# Arm_controller_Mega.net
KiCad netlist of a schematic drawn in EAGLE
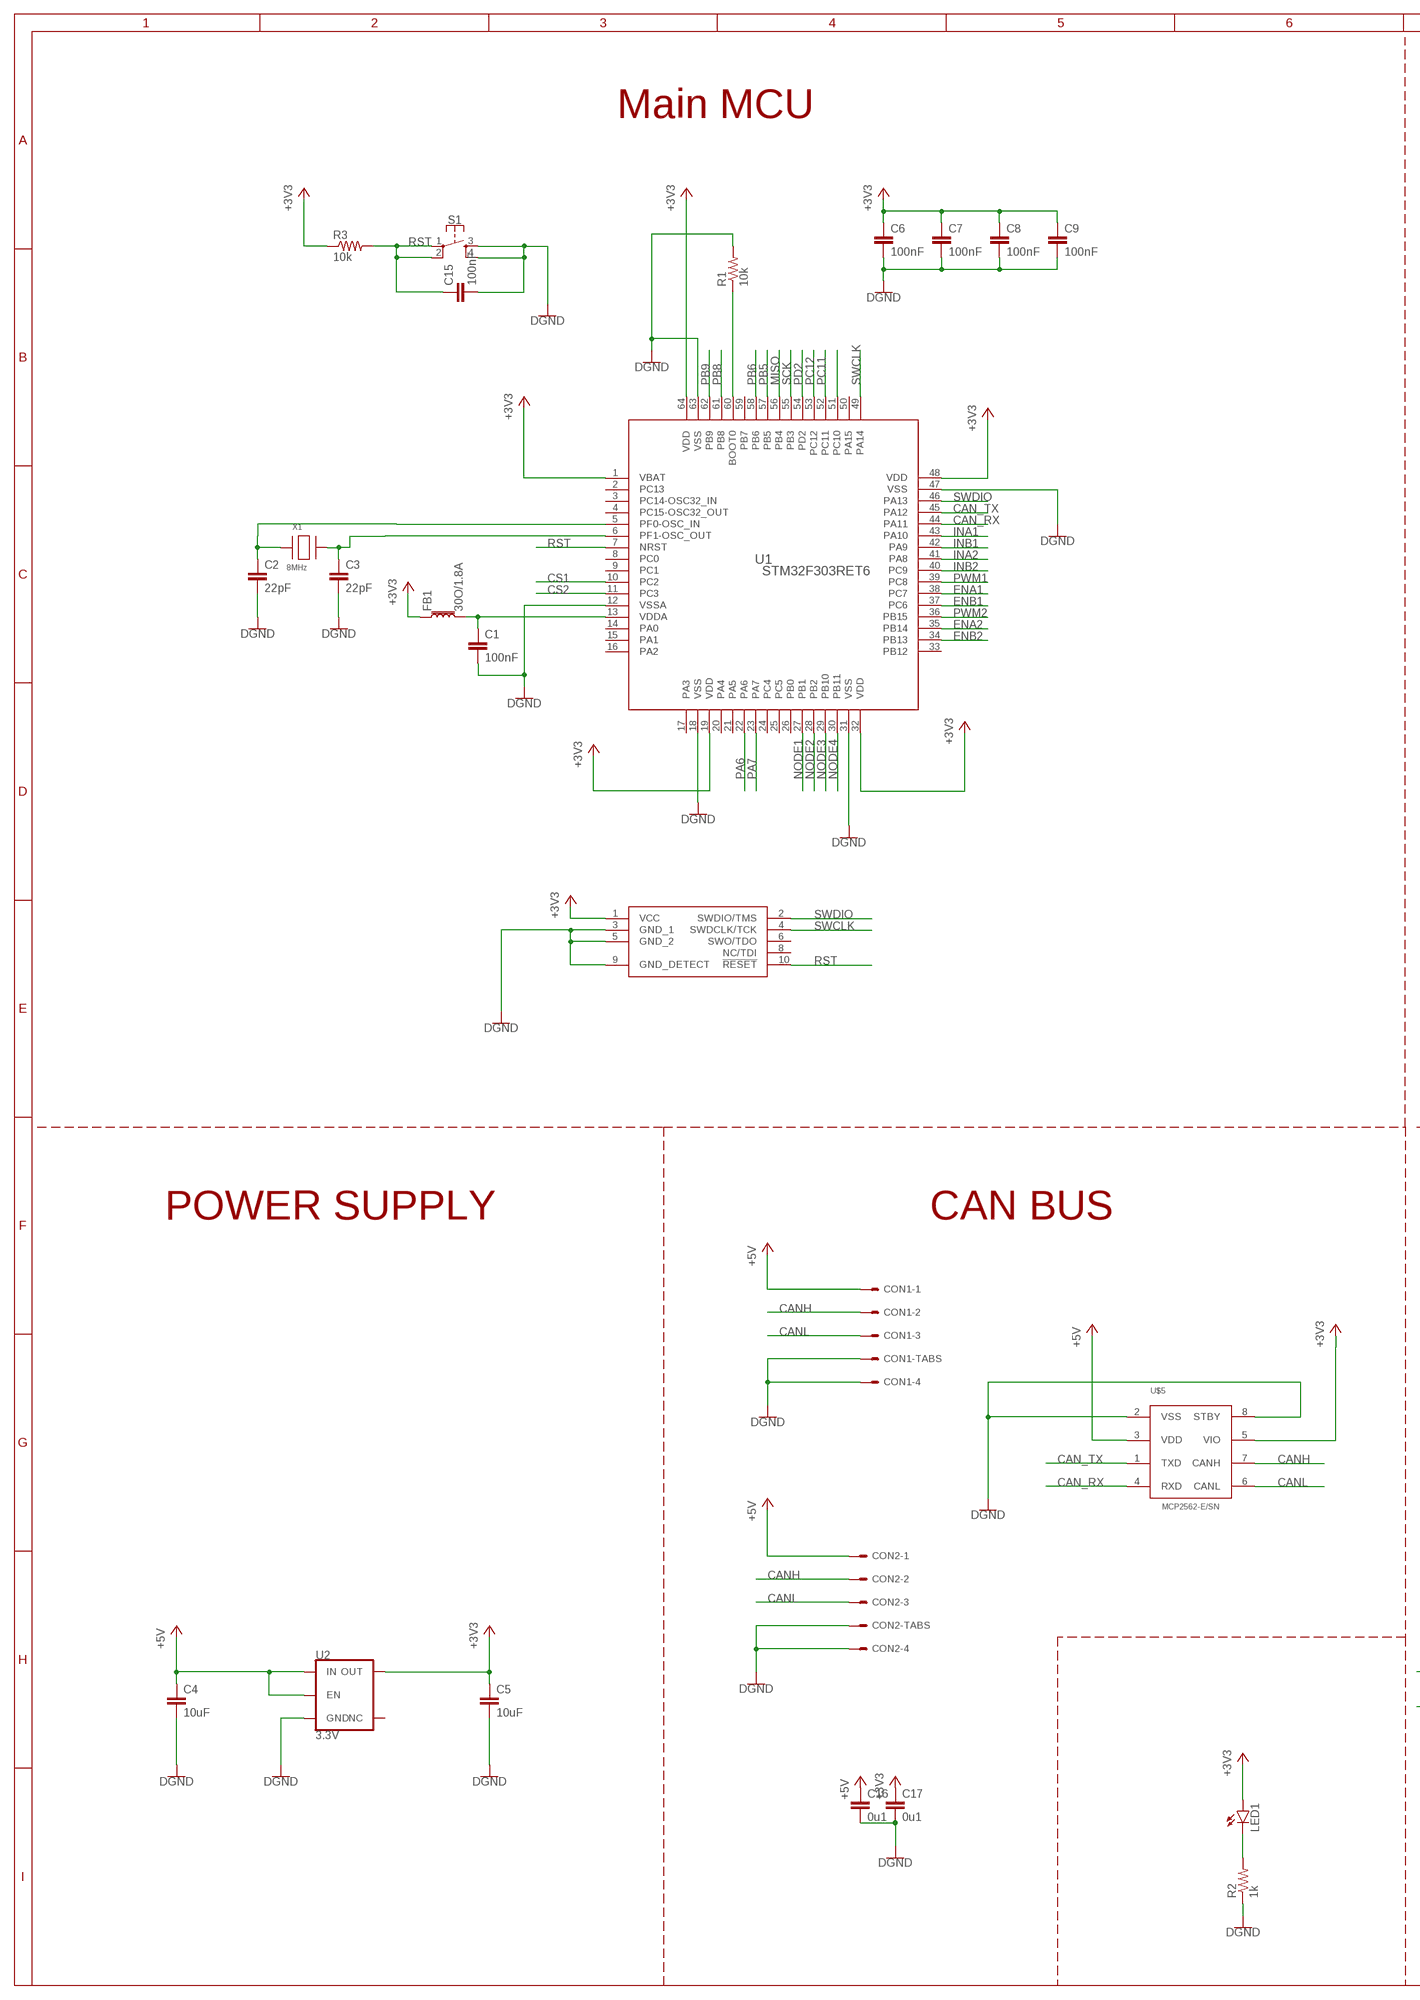
[diagram p0: schematic, sheet 1, part 1 of 2]
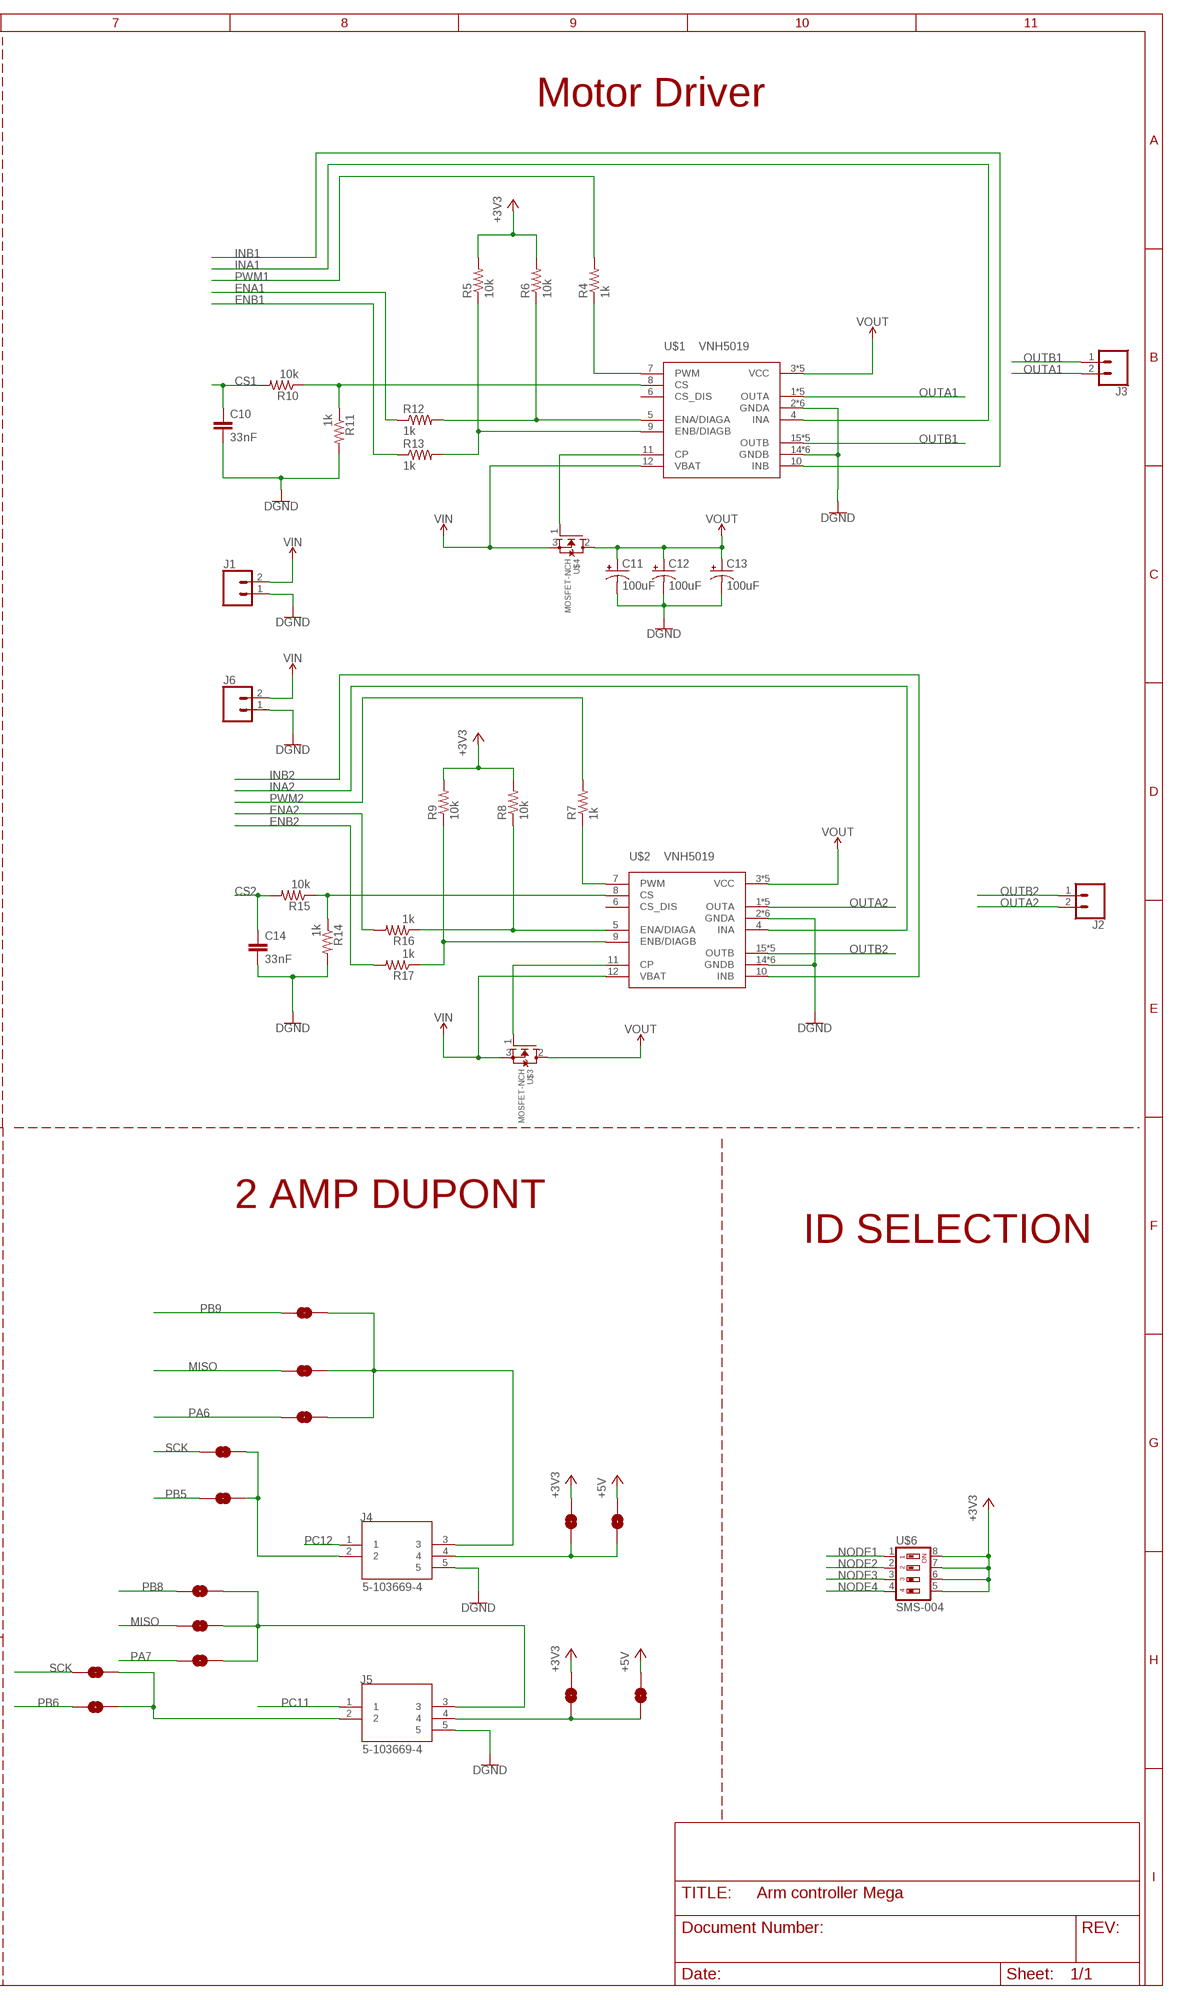
[diagram p1: schematic, sheet 1, part 2 of 2]

(export (version "E")
  (design (tool "Eeschema 10.0.6"))
  (components
    (comp (ref "C1")
      (value "100nF")
      (footprint "eagle-import:C0805")
      (libsource (lib "eagle-import") (part "C-EUC0805"))
    )
    (comp (ref "C2")
      (value "22pF")
      (footprint "eagle-import:C0805")
      (libsource (lib "eagle-import") (part "C-EUC0805"))
    )
    (comp (ref "C3")
      (value "22pF")
      (footprint "eagle-import:C0805")
      (libsource (lib "eagle-import") (part "C-EUC0805"))
    )
    (comp (ref "C4")
      (value "10uF")
      (footprint "eagle-import:C0805")
      (libsource (lib "eagle-import") (part "C-EUC0805"))
    )
    (comp (ref "C5")
      (value "10uF")
      (footprint "eagle-import:C0805")
      (libsource (lib "eagle-import") (part "C-EUC0805"))
    )
    (comp (ref "C6")
      (value "100nF")
      (footprint "eagle-import:C0805")
      (libsource (lib "eagle-import") (part "C-EUC0805"))
    )
    (comp (ref "C7")
      (value "100nF")
      (footprint "eagle-import:C0805")
      (libsource (lib "eagle-import") (part "C-EUC0805"))
    )
    (comp (ref "C8")
      (value "100nF")
      (footprint "eagle-import:C0805")
      (libsource (lib "eagle-import") (part "C-EUC0805"))
    )
    (comp (ref "C9")
      (value "100nF")
      (footprint "eagle-import:C0805")
      (libsource (lib "eagle-import") (part "C-EUC0805"))
    )
    (comp (ref "C10")
      (value "33nF")
      (footprint "eagle-import:C0805")
      (libsource (lib "eagle-import") (part "C-EUC0805"))
    )
    (comp (ref "C11")
      (value "100uF")
      (footprint "eagle-import:153CLV-0810")
      (libsource (lib "eagle-import") (part "CPOL-US153CLV-0810"))
    )
    (comp (ref "C12")
      (value "100uF")
      (footprint "eagle-import:153CLV-0810")
      (libsource (lib "eagle-import") (part "CPOL-US153CLV-0810"))
    )
    (comp (ref "C13")
      (value "100uF")
      (footprint "eagle-import:153CLV-0810")
      (libsource (lib "eagle-import") (part "CPOL-US153CLV-0810"))
    )
    (comp (ref "C14")
      (value "33nF")
      (footprint "eagle-import:C0805")
      (libsource (lib "eagle-import") (part "C-EUC0805"))
    )
    (comp (ref "C15")
      (value "100nF")
      (footprint "eagle-import:C0805")
      (libsource (lib "eagle-import") (part "C-EUC0805"))
    )
    (comp (ref "C16")
      (value "0u1")
      (footprint "eagle-import:C0805")
      (libsource (lib "eagle-import") (part "resistor_348_C-EUC0805"))
    )
    (comp (ref "C17")
      (value "0u1")
      (footprint "eagle-import:C0805")
      (libsource (lib "eagle-import") (part "resistor_348_C-EUC0805"))
    )
    (comp (ref "CON1")
      (value "SM04B-GHS-TB")
      (footprint "eagle-import:SM04B-GHS-TB")
      (libsource (lib "eagle-import") (part "SM04B-GHS-TB"))
    )
    (comp (ref "CON2")
      (value "SM04B-GHS-TB")
      (footprint "eagle-import:SM04B-GHS-TB")
      (libsource (lib "eagle-import") (part "SM04B-GHS-TB"))
    )
    (comp (ref "FB1")
      (value "30O/1.8A")
      (footprint "eagle-import:0603")
      (libsource (lib "eagle-import") (part "FERRITE_BEAD-0603"))
    )
    (comp (ref "J1")
      (value "CONN_025MM")
      (footprint "eagle-import:SCREWTERMINAL-5MM-2")
      (libsource (lib "eagle-import") (part "CONN_025MM"))
    )
    (comp (ref "J2")
      (value "CONN_025MM")
      (footprint "eagle-import:SCREWTERMINAL-5MM-2")
      (libsource (lib "eagle-import") (part "CONN_025MM"))
    )
    (comp (ref "J3")
      (value "CONN_025MM")
      (footprint "eagle-import:SCREWTERMINAL-5MM-2")
      (libsource (lib "eagle-import") (part "CONN_025MM"))
    )
    (comp (ref "J4")
      (value "5-103669-4")
      (footprint "eagle-import:TE_5-103669-4")
      (fields (field (name "MF") "TE Connectivity"))
      (libsource (lib "eagle-import") (part "5-103669-4"))
    )
    (comp (ref "J5")
      (value "5-103669-4")
      (footprint "eagle-import:TE_5-103669-4")
      (fields (field (name "MF") "TE Connectivity"))
      (libsource (lib "eagle-import") (part "5-103669-4"))
    )
    (comp (ref "J6")
      (value "CONN_025MM")
      (footprint "eagle-import:SCREWTERMINAL-5MM-2")
      (libsource (lib "eagle-import") (part "CONN_025MM"))
    )
    (comp (ref "JP1")
      (value "CORTEX-M-DBG")
      (footprint "eagle-import:FTSH-105-01-F-DV-007")
      (libsource (lib "eagle-import") (part "CORTEX-M-DBG"))
    )
    (comp (ref "JP2")
      (value "JUMPER-SMT_2_NO_NO-SILK")
      (footprint "eagle-import:SMT-JUMPER_2_NO_NO-SILK")
      (libsource (lib "eagle-import") (part "JUMPER-SMT_2_NO_NO-SILK"))
    )
    (comp (ref "JP3")
      (value "JUMPER-SMT_2_NO_NO-SILK")
      (footprint "eagle-import:SMT-JUMPER_2_NO_NO-SILK")
      (libsource (lib "eagle-import") (part "JUMPER-SMT_2_NO_NO-SILK"))
    )
    (comp (ref "JP4")
      (value "JUMPER-SMT_2_NO_NO-SILK")
      (footprint "eagle-import:SMT-JUMPER_2_NO_NO-SILK")
      (libsource (lib "eagle-import") (part "JUMPER-SMT_2_NO_NO-SILK"))
    )
    (comp (ref "JP5")
      (value "JUMPER-SMT_2_NO_NO-SILK")
      (footprint "eagle-import:SMT-JUMPER_2_NO_NO-SILK")
      (libsource (lib "eagle-import") (part "JUMPER-SMT_2_NO_NO-SILK"))
    )
    (comp (ref "JP6")
      (value "JUMPER-SMT_2_NO_NO-SILK")
      (footprint "eagle-import:SMT-JUMPER_2_NO_NO-SILK")
      (libsource (lib "eagle-import") (part "JUMPER-SMT_2_NO_NO-SILK"))
    )
    (comp (ref "JP7")
      (value "JUMPER-SMT_2_NO_NO-SILK")
      (footprint "eagle-import:SMT-JUMPER_2_NO_NO-SILK")
      (libsource (lib "eagle-import") (part "JUMPER-SMT_2_NO_NO-SILK"))
    )
    (comp (ref "JP8")
      (value "JUMPER-SMT_2_NO_NO-SILK")
      (footprint "eagle-import:SMT-JUMPER_2_NO_NO-SILK")
      (libsource (lib "eagle-import") (part "JUMPER-SMT_2_NO_NO-SILK"))
    )
    (comp (ref "JP9")
      (value "JUMPER-SMT_2_NO_NO-SILK")
      (footprint "eagle-import:SMT-JUMPER_2_NO_NO-SILK")
      (libsource (lib "eagle-import") (part "JUMPER-SMT_2_NO_NO-SILK"))
    )
    (comp (ref "JP10")
      (value "JUMPER-SMT_2_NO_NO-SILK")
      (footprint "eagle-import:SMT-JUMPER_2_NO_NO-SILK")
      (libsource (lib "eagle-import") (part "JUMPER-SMT_2_NO_NO-SILK"))
    )
    (comp (ref "JP11")
      (value "JUMPER-SMT_2_NO_NO-SILK")
      (footprint "eagle-import:SMT-JUMPER_2_NO_NO-SILK")
      (libsource (lib "eagle-import") (part "JUMPER-SMT_2_NO_NO-SILK"))
    )
    (comp (ref "JP12")
      (value "JUMPER-SMT_2_NO_NO-SILK")
      (footprint "eagle-import:SMT-JUMPER_2_NO_NO-SILK")
      (libsource (lib "eagle-import") (part "JUMPER-SMT_2_NO_NO-SILK"))
    )
    (comp (ref "JP13")
      (value "JUMPER-SMT_2_NO_NO-SILK")
      (footprint "eagle-import:SMT-JUMPER_2_NO_NO-SILK")
      (libsource (lib "eagle-import") (part "JUMPER-SMT_2_NO_NO-SILK"))
    )
    (comp (ref "JP14")
      (value "JUMPER-SMT_2_NO_NO-SILK")
      (footprint "eagle-import:SMT-JUMPER_2_NO_NO-SILK")
      (libsource (lib "eagle-import") (part "JUMPER-SMT_2_NO_NO-SILK"))
    )
    (comp (ref "JP15")
      (value "JUMPER-SMT_2_NO_NO-SILK")
      (footprint "eagle-import:SMT-JUMPER_2_NO_NO-SILK")
      (libsource (lib "eagle-import") (part "JUMPER-SMT_2_NO_NO-SILK"))
    )
    (comp (ref "LED1")
      (value "LEDCHIPLED_0805")
      (footprint "eagle-import:CHIPLED_0805")
      (libsource (lib "eagle-import") (part "LEDCHIPLED_0805"))
    )
    (comp (ref "R1")
      (value "10k")
      (footprint "eagle-import:R0805")
      (libsource (lib "eagle-import") (part "R-US_R0805"))
    )
    (comp (ref "R2")
      (value "1k")
      (footprint "eagle-import:R0805")
      (libsource (lib "eagle-import") (part "R-US_R0805"))
    )
    (comp (ref "R3")
      (value "10k")
      (footprint "eagle-import:R0805")
      (libsource (lib "eagle-import") (part "R-US_R0805"))
    )
    (comp (ref "R4")
      (value "1k")
      (footprint "eagle-import:R0805")
      (libsource (lib "eagle-import") (part "R-US_R0805"))
    )
    (comp (ref "R5")
      (value "10k")
      (footprint "eagle-import:R0805")
      (libsource (lib "eagle-import") (part "R-US_R0805"))
    )
    (comp (ref "R6")
      (value "10k")
      (footprint "eagle-import:R0805")
      (libsource (lib "eagle-import") (part "R-US_R0805"))
    )
    (comp (ref "R7")
      (value "1k")
      (footprint "eagle-import:R0805")
      (libsource (lib "eagle-import") (part "R-US_R0805"))
    )
    (comp (ref "R8")
      (value "10k")
      (footprint "eagle-import:R0805")
      (libsource (lib "eagle-import") (part "R-US_R0805"))
    )
    (comp (ref "R9")
      (value "10k")
      (footprint "eagle-import:R0805")
      (libsource (lib "eagle-import") (part "R-US_R0805"))
    )
    (comp (ref "R10")
      (value "10k")
      (footprint "eagle-import:R0805")
      (libsource (lib "eagle-import") (part "R-US_R0805"))
    )
    (comp (ref "R11")
      (value "1k")
      (footprint "eagle-import:R0805")
      (libsource (lib "eagle-import") (part "R-US_R0805"))
    )
    (comp (ref "R12")
      (value "1k")
      (footprint "eagle-import:R0805")
      (libsource (lib "eagle-import") (part "R-US_R0805"))
    )
    (comp (ref "R13")
      (value "1k")
      (footprint "eagle-import:R0805")
      (libsource (lib "eagle-import") (part "R-US_R0805"))
    )
    (comp (ref "R14")
      (value "1k")
      (footprint "eagle-import:R0805")
      (libsource (lib "eagle-import") (part "R-US_R0805"))
    )
    (comp (ref "R15")
      (value "10k")
      (footprint "eagle-import:R0805")
      (libsource (lib "eagle-import") (part "R-US_R0805"))
    )
    (comp (ref "R16")
      (value "1k")
      (footprint "eagle-import:R0805")
      (libsource (lib "eagle-import") (part "R-US_R0805"))
    )
    (comp (ref "R17")
      (value "1k")
      (footprint "eagle-import:R0805")
      (libsource (lib "eagle-import") (part "R-US_R0805"))
    )
    (comp (ref "S1")
      (value "MOMENTARY-SWITCH-SPST-2-SMD-5.2MM")
      (footprint "eagle-import:TACTILE_SWITCH_SMD_5.2MM")
      (libsource (lib "eagle-import") (part "MOMENTARY-SWITCH-SPST-2-SMD-5.2MM"))
    )
    (comp (ref "U$1")
      (value "VNH5019")
      (footprint "eagle-import:MULTIPOWERSO-30")
      (libsource (lib "eagle-import") (part "VNH5019"))
    )
    (comp (ref "U$2")
      (value "VNH5019")
      (footprint "eagle-import:MULTIPOWERSO-30")
      (libsource (lib "eagle-import") (part "VNH5019"))
    )
    (comp (ref "U$3")
      (value "MOSFET-NCH")
      (footprint "eagle-import:TO252-3")
      (libsource (lib "eagle-import") (part "MOSFET-NCH"))
    )
    (comp (ref "U$4")
      (value "MOSFET-NCH")
      (footprint "eagle-import:TO252-3")
      (libsource (lib "eagle-import") (part "MOSFET-NCH"))
    )
    (comp (ref "U$5")
      (value "MCP2562-E/SN")
      (footprint "eagle-import:SOIC8")
      (libsource (lib "eagle-import") (part "MCP2562-E/SN"))
    )
    (comp (ref "U$6")
      (value "SMS-004")
      (footprint "eagle-import:SMS-004")
      (libsource (lib "eagle-import") (part "SMS-004"))
    )
    (comp (ref "U1")
      (value "STM32F303RET6")
      (footprint "eagle-import:LQFP64-10X10MM")
      (fields (field (name "MANUFACTURER_PART_NUMBER") "stm32f302_303r2"))
      (libsource (lib "eagle-import") (part "STM32F303RET6"))
    )
    (comp (ref "U2")
      (value "3.3V")
      (footprint "eagle-import:SOT23-5")
      (libsource (lib "eagle-import") (part "V_REG_AP2112K-3.3V"))
    )
    (comp (ref "X1")
      (value "8MHz")
      (footprint "eagle-import:NX5032")
      (libsource (lib "eagle-import") (part "XTALNX5032"))
    )
  )
  (nets
    (net (code "1") (name "+3V3") (class "Default")
      (node (ref "C17") (pin "1") (pinfunction "1_1") (pintype "passive"))
      (node (ref "C5") (pin "1") (pinfunction "1_1") (pintype "passive"))
      (node (ref "C6") (pin "1") (pinfunction "1_1") (pintype "passive"))
      (node (ref "C7") (pin "1") (pinfunction "1_1") (pintype "passive"))
      (node (ref "C8") (pin "1") (pinfunction "1_1") (pintype "passive"))
      (node (ref "C9") (pin "1") (pinfunction "1_1") (pintype "passive"))
      (node (ref "FB1") (pin "1") (pinfunction "1_1") (pintype "passive"))
      (node (ref "JP1") (pin "1") (pinfunction "VCC_1") (pintype "bidirectional"))
      (node (ref "JP2") (pin "2") (pinfunction "2_2") (pintype "passive"))
      (node (ref "JP4") (pin "2") (pinfunction "2_2") (pintype "passive"))
      (node (ref "LED1") (pin "A") (pinfunction "A_A") (pintype "passive"))
      (node (ref "R3") (pin "1") (pinfunction "1_1") (pintype "passive"))
      (node (ref "R5") (pin "2") (pinfunction "2_2") (pintype "passive"))
      (node (ref "R6") (pin "2") (pinfunction "2_2") (pintype "passive"))
      (node (ref "R8") (pin "2") (pinfunction "2_2") (pintype "passive"))
      (node (ref "R9") (pin "2") (pinfunction "2_2") (pintype "passive"))
      (node (ref "U$5") (pin "5") (pinfunction "VIO_5") (pintype "bidirectional"))
      (node (ref "U$6") (pin "5") (pinfunction "5_5") (pintype "passive"))
      (node (ref "U$6") (pin "6") (pinfunction "6_6") (pintype "passive"))
      (node (ref "U$6") (pin "7") (pinfunction "7_7") (pintype "passive"))
      (node (ref "U$6") (pin "8") (pinfunction "8_8") (pintype "passive"))
      (node (ref "U1") (pin "1") (pinfunction "VBAT_1") (pintype "power_in"))
      (node (ref "U1") (pin "19") (pinfunction "VDD_19") (pintype "power_in"))
      (node (ref "U1") (pin "32") (pinfunction "VDD_32") (pintype "power_in"))
      (node (ref "U1") (pin "48") (pinfunction "VDD_48") (pintype "power_in"))
      (node (ref "U1") (pin "64") (pinfunction "VDD_64") (pintype "power_in"))
      (node (ref "U2") (pin "5") (pinfunction "OUT_5") (pintype "passive"))
    )
    (net (code "2") (name "+5V") (class "Default")
      (node (ref "C16") (pin "1") (pinfunction "1_1") (pintype "passive"))
      (node (ref "C4") (pin "1") (pinfunction "1_1") (pintype "passive"))
      (node (ref "CON1") (pin "P$1") (pinfunction "S_P$1") (pintype "passive"))
      (node (ref "CON2") (pin "P$1") (pinfunction "S_P$1") (pintype "passive"))
      (node (ref "JP3") (pin "2") (pinfunction "2_2") (pintype "passive"))
      (node (ref "JP6") (pin "2") (pinfunction "2_2") (pintype "passive"))
      (node (ref "U$5") (pin "3") (pinfunction "VDD_3") (pintype "bidirectional"))
      (node (ref "U2") (pin "1") (pinfunction "IN_1") (pintype "input"))
      (node (ref "U2") (pin "3") (pinfunction "EN_3") (pintype "input"))
    )
    (net (code "3") (name "/CANH") (class "Default")
      (node (ref "CON1") (pin "P$2") (pinfunction "S_P$2") (pintype "passive"))
      (node (ref "CON2") (pin "P$2") (pinfunction "S_P$2") (pintype "passive"))
      (node (ref "U$5") (pin "7") (pinfunction "CANH_7") (pintype "bidirectional"))
    )
    (net (code "4") (name "/CANL") (class "Default")
      (node (ref "CON1") (pin "P$3") (pinfunction "S_P$3") (pintype "passive"))
      (node (ref "CON2") (pin "P$3") (pinfunction "S_P$3") (pintype "passive"))
      (node (ref "U$5") (pin "6") (pinfunction "CANL_6") (pintype "bidirectional"))
    )
    (net (code "5") (name "/CAN_RX") (class "Default")
      (node (ref "U$5") (pin "4") (pinfunction "RXD_4") (pintype "bidirectional"))
      (node (ref "U1") (pin "44") (pinfunction "PA11_44") (pintype "bidirectional"))
    )
    (net (code "6") (name "/CAN_TX") (class "Default")
      (node (ref "U$5") (pin "1") (pinfunction "TXD_1") (pintype "bidirectional"))
      (node (ref "U1") (pin "45") (pinfunction "PA12_45") (pintype "bidirectional"))
    )
    (net (code "7") (name "/CS1") (class "Default")
      (node (ref "C10") (pin "1") (pinfunction "1_1") (pintype "passive"))
      (node (ref "R10") (pin "2") (pinfunction "2_2") (pintype "passive"))
      (node (ref "U1") (pin "10") (pinfunction "PC2_10") (pintype "bidirectional"))
    )
    (net (code "8") (name "/CS2") (class "Default")
      (node (ref "C14") (pin "1") (pinfunction "1_1") (pintype "passive"))
      (node (ref "R15") (pin "2") (pinfunction "2_2") (pintype "passive"))
      (node (ref "U1") (pin "11") (pinfunction "PC3_11") (pintype "bidirectional"))
    )
    (net (code "9") (name "/ENA1") (class "Default")
      (node (ref "R12") (pin "1") (pinfunction "1_1") (pintype "passive"))
      (node (ref "U1") (pin "38") (pinfunction "PC7_38") (pintype "bidirectional"))
    )
    (net (code "10") (name "/ENA2") (class "Default")
      (node (ref "R16") (pin "2") (pinfunction "2_2") (pintype "passive"))
      (node (ref "U1") (pin "35") (pinfunction "PB14_35") (pintype "bidirectional"))
    )
    (net (code "11") (name "/ENB1") (class "Default")
      (node (ref "R13") (pin "1") (pinfunction "1_1") (pintype "passive"))
      (node (ref "U1") (pin "37") (pinfunction "PC6_37") (pintype "bidirectional"))
    )
    (net (code "12") (name "/ENB2") (class "Default")
      (node (ref "R17") (pin "2") (pinfunction "2_2") (pintype "passive"))
      (node (ref "U1") (pin "34") (pinfunction "PB13_34") (pintype "bidirectional"))
    )
    (net (code "13") (name "/INA1") (class "Default")
      (node (ref "U$1") (pin "4") (pinfunction "INA_4") (pintype "bidirectional"))
      (node (ref "U1") (pin "43") (pinfunction "PA10_43") (pintype "bidirectional"))
    )
    (net (code "14") (name "/INA2") (class "Default")
      (node (ref "U$2") (pin "4") (pinfunction "INA_4") (pintype "bidirectional"))
      (node (ref "U1") (pin "41") (pinfunction "PA8_41") (pintype "bidirectional"))
    )
    (net (code "15") (name "/INB1") (class "Default")
      (node (ref "U$1") (pin "10") (pinfunction "INB_10") (pintype "bidirectional"))
      (node (ref "U1") (pin "42") (pinfunction "PA9_42") (pintype "bidirectional"))
    )
    (net (code "16") (name "/INB2") (class "Default")
      (node (ref "U$2") (pin "10") (pinfunction "INB_10") (pintype "bidirectional"))
      (node (ref "U1") (pin "40") (pinfunction "PC9_40") (pintype "bidirectional"))
    )
    (net (code "17") (name "/MISO") (class "Default")
      (node (ref "JP12") (pin "2") (pinfunction "2_2") (pintype "passive"))
      (node (ref "JP5") (pin "2") (pinfunction "2_2") (pintype "passive"))
      (node (ref "U1") (pin "56") (pinfunction "PB4_56") (pintype "bidirectional"))
    )
    (net (code "18") (name "/NODE1") (class "Default")
      (node (ref "U$6") (pin "1") (pinfunction "1_1") (pintype "passive"))
      (node (ref "U1") (pin "27") (pinfunction "PB1_27") (pintype "bidirectional"))
    )
    (net (code "19") (name "/NODE2") (class "Default")
      (node (ref "U$6") (pin "2") (pinfunction "2_2") (pintype "passive"))
      (node (ref "U1") (pin "28") (pinfunction "PB2_28") (pintype "bidirectional"))
    )
    (net (code "20") (name "/NODE3") (class "Default")
      (node (ref "U$6") (pin "3") (pinfunction "3_3") (pintype "passive"))
      (node (ref "U1") (pin "29") (pinfunction "PB10_29") (pintype "bidirectional"))
    )
    (net (code "21") (name "/NODE4") (class "Default")
      (node (ref "U$6") (pin "4") (pinfunction "4_4") (pintype "passive"))
      (node (ref "U1") (pin "30") (pinfunction "PB11_30") (pintype "bidirectional"))
    )
    (net (code "22") (name "/OUTA1") (class "Default")
      (node (ref "J3") (pin "2") (pinfunction "2_2") (pintype "passive"))
      (node (ref "U$1") (pin "1") (pinfunction "OUTA_1") (pintype "bidirectional"))
      (node (ref "U$1") (pin "25") (pinfunction "OUTA_25") (pintype "bidirectional"))
      (node (ref "U$1") (pin "30") (pinfunction "OUTA_30") (pintype "bidirectional"))
      (node (ref "U$1") (pin "OUTA") (pinfunction "OUTA_OUTA") (pintype "bidirectional"))
      (node (ref "U$1") (pin "OUTA@1") (pinfunction "OUTA_OUTA@1") (pintype "bidirectional"))
    )
    (net (code "23") (name "/OUTA2") (class "Default")
      (node (ref "J2") (pin "2") (pinfunction "2_2") (pintype "passive"))
      (node (ref "U$2") (pin "1") (pinfunction "OUTA_1") (pintype "bidirectional"))
      (node (ref "U$2") (pin "25") (pinfunction "OUTA_25") (pintype "bidirectional"))
      (node (ref "U$2") (pin "30") (pinfunction "OUTA_30") (pintype "bidirectional"))
      (node (ref "U$2") (pin "OUTA") (pinfunction "OUTA_OUTA") (pintype "bidirectional"))
      (node (ref "U$2") (pin "OUTA@1") (pinfunction "OUTA_OUTA@1") (pintype "bidirectional"))
    )
    (net (code "24") (name "/OUTB1") (class "Default")
      (node (ref "J3") (pin "1") (pinfunction "1_1") (pintype "passive"))
      (node (ref "U$1") (pin "15") (pinfunction "OUTB_15") (pintype "bidirectional"))
      (node (ref "U$1") (pin "16") (pinfunction "OUTB_16") (pintype "bidirectional"))
      (node (ref "U$1") (pin "21") (pinfunction "OUTB_21") (pintype "bidirectional"))
      (node (ref "U$1") (pin "OUTB") (pinfunction "OUTB_OUTB") (pintype "bidirectional"))
      (node (ref "U$1") (pin "OUTB@1") (pinfunction "OUTB_OUTB@1") (pintype "bidirectional"))
    )
    (net (code "25") (name "/OUTB2") (class "Default")
      (node (ref "J2") (pin "1") (pinfunction "1_1") (pintype "passive"))
      (node (ref "U$2") (pin "15") (pinfunction "OUTB_15") (pintype "bidirectional"))
      (node (ref "U$2") (pin "16") (pinfunction "OUTB_16") (pintype "bidirectional"))
      (node (ref "U$2") (pin "21") (pinfunction "OUTB_21") (pintype "bidirectional"))
      (node (ref "U$2") (pin "OUTB") (pinfunction "OUTB_OUTB") (pintype "bidirectional"))
      (node (ref "U$2") (pin "OUTB@1") (pinfunction "OUTB_OUTB@1") (pintype "bidirectional"))
    )
    (net (code "26") (name "/PA6") (class "Default")
      (node (ref "JP7") (pin "2") (pinfunction "2_2") (pintype "passive"))
      (node (ref "U1") (pin "22") (pinfunction "PA6_22") (pintype "bidirectional"))
    )
    (net (code "27") (name "/PA7") (class "Default")
      (node (ref "JP13") (pin "2") (pinfunction "2_2") (pintype "passive"))
      (node (ref "U1") (pin "23") (pinfunction "PA7_23") (pintype "bidirectional"))
    )
    (net (code "28") (name "/PB5") (class "Default")
      (node (ref "JP9") (pin "2") (pinfunction "2_2") (pintype "passive"))
      (node (ref "U1") (pin "57") (pinfunction "PB5_57") (pintype "bidirectional"))
    )
    (net (code "29") (name "/PB6") (class "Default")
      (node (ref "JP14") (pin "2") (pinfunction "2_2") (pintype "passive"))
      (node (ref "U1") (pin "58") (pinfunction "PB6_58") (pintype "bidirectional"))
    )
    (net (code "30") (name "/PB8") (class "Default")
      (node (ref "JP11") (pin "2") (pinfunction "2_2") (pintype "passive"))
      (node (ref "U1") (pin "61") (pinfunction "PB8_61") (pintype "bidirectional"))
    )
    (net (code "31") (name "/PB9") (class "Default")
      (node (ref "JP8") (pin "2") (pinfunction "2_2") (pintype "passive"))
      (node (ref "U1") (pin "62") (pinfunction "PB9_62") (pintype "bidirectional"))
    )
    (net (code "32") (name "/PC11") (class "Default")
      (node (ref "J5") (pin "1") (pinfunction "1_1") (pintype "passive"))
      (node (ref "U1") (pin "52") (pinfunction "PC11_52") (pintype "bidirectional"))
    )
    (net (code "33") (name "/PC12") (class "Default")
      (node (ref "J4") (pin "1") (pinfunction "1_1") (pintype "passive"))
      (node (ref "U1") (pin "53") (pinfunction "PC12_53") (pintype "bidirectional"))
    )
    (net (code "34") (name "/PD2") (class "Default")
      (node (ref "U1") (pin "54") (pinfunction "PD2_54") (pintype "bidirectional"))
    )
    (net (code "35") (name "/PWM1") (class "Default")
      (node (ref "R4") (pin "2") (pinfunction "2_2") (pintype "passive"))
      (node (ref "U1") (pin "39") (pinfunction "PC8_39") (pintype "bidirectional"))
    )
    (net (code "36") (name "/PWM2") (class "Default")
      (node (ref "R7") (pin "2") (pinfunction "2_2") (pintype "passive"))
      (node (ref "U1") (pin "36") (pinfunction "PB15_36") (pintype "bidirectional"))
    )
    (net (code "37") (name "/RST") (class "Default")
      (node (ref "C15") (pin "1") (pinfunction "1_1") (pintype "passive"))
      (node (ref "JP1") (pin "10") (pinfunction "~{RESET}_10") (pintype "bidirectional"))
      (node (ref "R3") (pin "2") (pinfunction "2_2") (pintype "passive"))
      (node (ref "S1") (pin "1") (pinfunction "1_1") (pintype "passive"))
      (node (ref "S1") (pin "2") (pinfunction "2_2") (pintype "passive"))
      (node (ref "U1") (pin "7") (pinfunction "NRST_7") (pintype "bidirectional"))
    )
    (net (code "38") (name "/SCK") (class "Default")
      (node (ref "JP10") (pin "2") (pinfunction "2_2") (pintype "passive"))
      (node (ref "JP15") (pin "2") (pinfunction "2_2") (pintype "passive"))
      (node (ref "U1") (pin "55") (pinfunction "PB3_55") (pintype "bidirectional"))
    )
    (net (code "39") (name "/SWCLK") (class "Default")
      (node (ref "JP1") (pin "4") (pinfunction "SWDCLK/TCK_4") (pintype "bidirectional"))
      (node (ref "U1") (pin "49") (pinfunction "PA14_49") (pintype "bidirectional"))
    )
    (net (code "40") (name "/SWDIO") (class "Default")
      (node (ref "JP1") (pin "2") (pinfunction "SWDIO/TMS_2") (pintype "bidirectional"))
      (node (ref "U1") (pin "46") (pinfunction "PA13_46") (pintype "bidirectional"))
    )
    (net (code "41") (name "DGND") (class "Default")
      (node (ref "C1") (pin "2") (pinfunction "2_2") (pintype "passive"))
      (node (ref "C10") (pin "2") (pinfunction "2_2") (pintype "passive"))
      (node (ref "C11") (pin "-") (pinfunction "-_-") (pintype "passive"))
      (node (ref "C12") (pin "-") (pinfunction "-_-") (pintype "passive"))
      (node (ref "C13") (pin "-") (pinfunction "-_-") (pintype "passive"))
      (node (ref "C14") (pin "2") (pinfunction "2_2") (pintype "passive"))
      (node (ref "C15") (pin "2") (pinfunction "2_2") (pintype "passive"))
      (node (ref "C16") (pin "2") (pinfunction "2_2") (pintype "passive"))
      (node (ref "C17") (pin "2") (pinfunction "2_2") (pintype "passive"))
      (node (ref "C2") (pin "2") (pinfunction "2_2") (pintype "passive"))
      (node (ref "C3") (pin "2") (pinfunction "2_2") (pintype "passive"))
      (node (ref "C4") (pin "2") (pinfunction "2_2") (pintype "passive"))
      (node (ref "C5") (pin "2") (pinfunction "2_2") (pintype "passive"))
      (node (ref "C6") (pin "2") (pinfunction "2_2") (pintype "passive"))
      (node (ref "C7") (pin "2") (pinfunction "2_2") (pintype "passive"))
      (node (ref "C8") (pin "2") (pinfunction "2_2") (pintype "passive"))
      (node (ref "C9") (pin "2") (pinfunction "2_2") (pintype "passive"))
      (node (ref "CON1") (pin "P$4") (pinfunction "S_P$4") (pintype "passive"))
      (node (ref "CON1") (pin "P$5") (pinfunction "S_P$5") (pintype "passive"))
      (node (ref "CON1") (pin "P$6") (pinfunction "S_P$6") (pintype "passive"))
      (node (ref "CON2") (pin "P$4") (pinfunction "S_P$4") (pintype "passive"))
      (node (ref "CON2") (pin "P$5") (pinfunction "S_P$5") (pintype "passive"))
      (node (ref "CON2") (pin "P$6") (pinfunction "S_P$6") (pintype "passive"))
      (node (ref "J1") (pin "1") (pinfunction "1_1") (pintype "passive"))
      (node (ref "J4") (pin "5") (pinfunction "5_5") (pintype "passive"))
      (node (ref "J5") (pin "5") (pinfunction "5_5") (pintype "passive"))
      (node (ref "J6") (pin "1") (pinfunction "1_1") (pintype "passive"))
      (node (ref "JP1") (pin "3") (pinfunction "GND_1_3") (pintype "bidirectional"))
      (node (ref "JP1") (pin "5") (pinfunction "GND_2_5") (pintype "bidirectional"))
      (node (ref "JP1") (pin "9") (pinfunction "GND_DETECT_9") (pintype "bidirectional"))
      (node (ref "R1") (pin "2") (pinfunction "2_2") (pintype "passive"))
      (node (ref "R11") (pin "2") (pinfunction "2_2") (pintype "passive"))
      (node (ref "R14") (pin "2") (pinfunction "2_2") (pintype "passive"))
      (node (ref "R2") (pin "1") (pinfunction "1_1") (pintype "passive"))
      (node (ref "S1") (pin "3") (pinfunction "3_3") (pintype "passive"))
      (node (ref "S1") (pin "4") (pinfunction "4_4") (pintype "passive"))
      (node (ref "U$1") (pin "14") (pinfunction "GNDB_14") (pintype "bidirectional"))
      (node (ref "U$1") (pin "17") (pinfunction "GNDB_17") (pintype "bidirectional"))
      (node (ref "U$1") (pin "18") (pinfunction "GNDB_18") (pintype "bidirectional"))
      (node (ref "U$1") (pin "19") (pinfunction "GNDB_19") (pintype "bidirectional"))
      (node (ref "U$1") (pin "2") (pinfunction "GNDA_2") (pintype "bidirectional"))
      (node (ref "U$1") (pin "20") (pinfunction "GNDB_20") (pintype "bidirectional"))
      (node (ref "U$1") (pin "22") (pinfunction "GNDA_22") (pintype "bidirectional"))
      (node (ref "U$1") (pin "24") (pinfunction "GNDB_24") (pintype "bidirectional"))
      (node (ref "U$1") (pin "26") (pinfunction "GNDA_26") (pintype "bidirectional"))
      (node (ref "U$1") (pin "27") (pinfunction "GNDA_27") (pintype "bidirectional"))
      (node (ref "U$1") (pin "28") (pinfunction "GNDA_28") (pintype "bidirectional"))
      (node (ref "U$1") (pin "29") (pinfunction "GNDA_29") (pintype "bidirectional"))
      (node (ref "U$2") (pin "14") (pinfunction "GNDB_14") (pintype "bidirectional"))
      (node (ref "U$2") (pin "17") (pinfunction "GNDB_17") (pintype "bidirectional"))
      (node (ref "U$2") (pin "18") (pinfunction "GNDB_18") (pintype "bidirectional"))
      (node (ref "U$2") (pin "19") (pinfunction "GNDB_19") (pintype "bidirectional"))
      (node (ref "U$2") (pin "2") (pinfunction "GNDA_2") (pintype "bidirectional"))
      (node (ref "U$2") (pin "20") (pinfunction "GNDB_20") (pintype "bidirectional"))
      (node (ref "U$2") (pin "22") (pinfunction "GNDA_22") (pintype "bidirectional"))
      (node (ref "U$2") (pin "24") (pinfunction "GNDB_24") (pintype "bidirectional"))
      (node (ref "U$2") (pin "26") (pinfunction "GNDA_26") (pintype "bidirectional"))
      (node (ref "U$2") (pin "27") (pinfunction "GNDA_27") (pintype "bidirectional"))
      (node (ref "U$2") (pin "28") (pinfunction "GNDA_28") (pintype "bidirectional"))
      (node (ref "U$2") (pin "29") (pinfunction "GNDA_29") (pintype "bidirectional"))
      (node (ref "U$5") (pin "2") (pinfunction "VSS_2") (pintype "bidirectional"))
      (node (ref "U$5") (pin "8") (pinfunction "STBY_8") (pintype "bidirectional"))
      (node (ref "U1") (pin "12") (pinfunction "VSSA_12") (pintype "power_in"))
      (node (ref "U1") (pin "18") (pinfunction "VSS_18") (pintype "power_in"))
      (node (ref "U1") (pin "31") (pinfunction "VSS_31") (pintype "power_in"))
      (node (ref "U1") (pin "47") (pinfunction "VSS_47") (pintype "power_in"))
      (node (ref "U1") (pin "63") (pinfunction "VSS_63") (pintype "power_in"))
      (node (ref "U2") (pin "2") (pinfunction "GND_2") (pintype "input"))
    )
    (net (code "42") (name "Net-(J4-Pad2)") (class "Default")
      (node (ref "J4") (pin "2") (pinfunction "2_2") (pintype "passive"))
      (node (ref "JP10") (pin "1") (pinfunction "1_1") (pintype "passive"))
      (node (ref "JP9") (pin "1") (pinfunction "1_1") (pintype "passive"))
    )
    (net (code "43") (name "Net-(J4-Pad3)") (class "Default")
      (node (ref "J4") (pin "3") (pinfunction "3_3") (pintype "passive"))
      (node (ref "JP5") (pin "1") (pinfunction "1_1") (pintype "passive"))
      (node (ref "JP7") (pin "1") (pinfunction "1_1") (pintype "passive"))
      (node (ref "JP8") (pin "1") (pinfunction "1_1") (pintype "passive"))
    )
    (net (code "44") (name "Net-(J4-Pad4)") (class "Default")
      (node (ref "J4") (pin "4") (pinfunction "4_4") (pintype "passive"))
      (node (ref "JP4") (pin "1") (pinfunction "1_1") (pintype "passive"))
      (node (ref "JP6") (pin "1") (pinfunction "1_1") (pintype "passive"))
    )
    (net (code "45") (name "Net-(J5-Pad2)") (class "Default")
      (node (ref "J5") (pin "2") (pinfunction "2_2") (pintype "passive"))
      (node (ref "JP14") (pin "1") (pinfunction "1_1") (pintype "passive"))
      (node (ref "JP15") (pin "1") (pinfunction "1_1") (pintype "passive"))
    )
    (net (code "46") (name "Net-(J5-Pad3)") (class "Default")
      (node (ref "J5") (pin "3") (pinfunction "3_3") (pintype "passive"))
      (node (ref "JP11") (pin "1") (pinfunction "1_1") (pintype "passive"))
      (node (ref "JP12") (pin "1") (pinfunction "1_1") (pintype "passive"))
      (node (ref "JP13") (pin "1") (pinfunction "1_1") (pintype "passive"))
    )
    (net (code "47") (name "Net-(J5-Pad4)") (class "Default")
      (node (ref "J5") (pin "4") (pinfunction "4_4") (pintype "passive"))
      (node (ref "JP2") (pin "1") (pinfunction "1_1") (pintype "passive"))
      (node (ref "JP3") (pin "1") (pinfunction "1_1") (pintype "passive"))
    )
    (net (code "48") (name "Net-(LED1-PadC)") (class "Default")
      (node (ref "LED1") (pin "C") (pinfunction "C_C") (pintype "passive"))
      (node (ref "R2") (pin "2") (pinfunction "2_2") (pintype "passive"))
    )
    (net (code "49") (name "Net-(U$1-CP)") (class "Default")
      (node (ref "U$1") (pin "11") (pinfunction "CP_11") (pintype "bidirectional"))
      (node (ref "U$4") (pin "1") (pinfunction "G_1") (pintype "bidirectional"))
    )
    (net (code "50") (name "Net-(U$1-CS)") (class "Default")
      (node (ref "R10") (pin "1") (pinfunction "1_1") (pintype "passive"))
      (node (ref "R11") (pin "1") (pinfunction "1_1") (pintype "passive"))
      (node (ref "U$1") (pin "8") (pinfunction "CS_8") (pintype "bidirectional"))
    )
    (net (code "51") (name "Net-(U$1-ENA{slash}DIAGA)") (class "Default")
      (node (ref "R12") (pin "2") (pinfunction "2_2") (pintype "passive"))
      (node (ref "R6") (pin "1") (pinfunction "1_1") (pintype "passive"))
      (node (ref "U$1") (pin "5") (pinfunction "ENA/DIAGA_5") (pintype "bidirectional"))
    )
    (net (code "52") (name "Net-(U$1-ENB{slash}DIAGB)") (class "Default")
      (node (ref "R13") (pin "2") (pinfunction "2_2") (pintype "passive"))
      (node (ref "R5") (pin "1") (pinfunction "1_1") (pintype "passive"))
      (node (ref "U$1") (pin "9") (pinfunction "ENB/DIAGB_9") (pintype "bidirectional"))
    )
    (net (code "53") (name "Net-(U$1-PWM)") (class "Default")
      (node (ref "R4") (pin "1") (pinfunction "1_1") (pintype "passive"))
      (node (ref "U$1") (pin "7") (pinfunction "PWM_7") (pintype "bidirectional"))
    )
    (net (code "54") (name "Net-(U$2-CP)") (class "Default")
      (node (ref "U$2") (pin "11") (pinfunction "CP_11") (pintype "bidirectional"))
      (node (ref "U$3") (pin "1") (pinfunction "G_1") (pintype "bidirectional"))
    )
    (net (code "55") (name "Net-(U$2-CS)") (class "Default")
      (node (ref "R14") (pin "1") (pinfunction "1_1") (pintype "passive"))
      (node (ref "R15") (pin "1") (pinfunction "1_1") (pintype "passive"))
      (node (ref "U$2") (pin "8") (pinfunction "CS_8") (pintype "bidirectional"))
    )
    (net (code "56") (name "Net-(U$2-ENA{slash}DIAGA)") (class "Default")
      (node (ref "R16") (pin "1") (pinfunction "1_1") (pintype "passive"))
      (node (ref "R8") (pin "1") (pinfunction "1_1") (pintype "passive"))
      (node (ref "U$2") (pin "5") (pinfunction "ENA/DIAGA_5") (pintype "bidirectional"))
    )
    (net (code "57") (name "Net-(U$2-ENB{slash}DIAGB)") (class "Default")
      (node (ref "R17") (pin "1") (pinfunction "1_1") (pintype "passive"))
      (node (ref "R9") (pin "1") (pinfunction "1_1") (pintype "passive"))
      (node (ref "U$2") (pin "9") (pinfunction "ENB/DIAGB_9") (pintype "bidirectional"))
    )
    (net (code "58") (name "Net-(U$2-PWM)") (class "Default")
      (node (ref "R7") (pin "1") (pinfunction "1_1") (pintype "passive"))
      (node (ref "U$2") (pin "7") (pinfunction "PWM_7") (pintype "bidirectional"))
    )
    (net (code "59") (name "Net-(U1-BOOT0)") (class "Default")
      (node (ref "R1") (pin "1") (pinfunction "1_1") (pintype "passive"))
      (node (ref "U1") (pin "60") (pinfunction "BOOT0_60") (pintype "input"))
    )
    (net (code "60") (name "Net-(U1-PF0-OSC_IN)") (class "Default")
      (node (ref "C2") (pin "1") (pinfunction "1_1") (pintype "passive"))
      (node (ref "U1") (pin "5") (pinfunction "PF0-OSC_IN_5") (pintype "bidirectional"))
      (node (ref "X1") (pin "P$1") (pinfunction "P$1_P$1") (pintype "bidirectional"))
    )
    (net (code "61") (name "Net-(U1-PF1-OSC_OUT)") (class "Default")
      (node (ref "C3") (pin "1") (pinfunction "1_1") (pintype "passive"))
      (node (ref "U1") (pin "6") (pinfunction "PF1-OSC_OUT_6") (pintype "bidirectional"))
      (node (ref "X1") (pin "P$2") (pinfunction "P$2_P$2") (pintype "bidirectional"))
    )
    (net (code "62") (name "Net-(U1-VDDA)") (class "Default")
      (node (ref "C1") (pin "1") (pinfunction "1_1") (pintype "passive"))
      (node (ref "FB1") (pin "2") (pinfunction "2_2") (pintype "passive"))
      (node (ref "U1") (pin "13") (pinfunction "VDDA_13") (pintype "power_in"))
    )
    (net (code "63") (name "VIN") (class "Default")
      (node (ref "J1") (pin "2") (pinfunction "2_2") (pintype "passive"))
      (node (ref "J6") (pin "2") (pinfunction "2_2") (pintype "passive"))
      (node (ref "U$1") (pin "12") (pinfunction "VBAT_12") (pintype "bidirectional"))
      (node (ref "U$2") (pin "12") (pinfunction "VBAT_12") (pintype "bidirectional"))
      (node (ref "U$3") (pin "3") (pinfunction "S_3") (pintype "bidirectional"))
      (node (ref "U$4") (pin "3") (pinfunction "S_3") (pintype "bidirectional"))
    )
    (net (code "64") (name "VOUT") (class "Default")
      (node (ref "C11") (pin "+") (pinfunction "+_+") (pintype "passive"))
      (node (ref "C12") (pin "+") (pinfunction "+_+") (pintype "passive"))
      (node (ref "C13") (pin "+") (pinfunction "+_+") (pintype "passive"))
      (node (ref "U$1") (pin "13") (pinfunction "VCC_13") (pintype "bidirectional"))
      (node (ref "U$1") (pin "23") (pinfunction "VCC_23") (pintype "bidirectional"))
      (node (ref "U$1") (pin "3") (pinfunction "VCC_3") (pintype "bidirectional"))
      (node (ref "U$1") (pin "VCC") (pinfunction "VCC_VCC") (pintype "bidirectional"))
      (node (ref "U$1") (pin "VCC@1") (pinfunction "VCC_VCC@1") (pintype "bidirectional"))
      (node (ref "U$2") (pin "13") (pinfunction "VCC_13") (pintype "bidirectional"))
      (node (ref "U$2") (pin "23") (pinfunction "VCC_23") (pintype "bidirectional"))
      (node (ref "U$2") (pin "3") (pinfunction "VCC_3") (pintype "bidirectional"))
      (node (ref "U$2") (pin "VCC") (pinfunction "VCC_VCC") (pintype "bidirectional"))
      (node (ref "U$2") (pin "VCC@1") (pinfunction "VCC_VCC@1") (pintype "bidirectional"))
      (node (ref "U$3") (pin "2") (pinfunction "D_2") (pintype "bidirectional"))
      (node (ref "U$4") (pin "2") (pinfunction "D_2") (pintype "bidirectional"))
    )
    (net (code "65") (name "unconnected-(JP1-NC{slash}TDI-Pad8)") (class "Default")
      (node (ref "JP1") (pin "8") (pinfunction "NC/TDI_8") (pintype "bidirectional"))
    )
    (net (code "66") (name "unconnected-(JP1-SWO{slash}TDO-Pad6)") (class "Default")
      (node (ref "JP1") (pin "6") (pinfunction "SWO/TDO_6") (pintype "bidirectional"))
    )
    (net (code "67") (name "unconnected-(U$1-CS_DIS-Pad6)") (class "Default")
      (node (ref "U$1") (pin "6") (pinfunction "CS_DIS_6") (pintype "bidirectional"))
    )
    (net (code "68") (name "unconnected-(U$2-CS_DIS-Pad6)") (class "Default")
      (node (ref "U$2") (pin "6") (pinfunction "CS_DIS_6") (pintype "bidirectional"))
    )
    (net (code "69") (name "unconnected-(U1-PA0-Pad14)") (class "Default")
      (node (ref "U1") (pin "14") (pinfunction "PA0_14") (pintype "bidirectional"))
    )
    (net (code "70") (name "unconnected-(U1-PA1-Pad15)") (class "Default")
      (node (ref "U1") (pin "15") (pinfunction "PA1_15") (pintype "bidirectional"))
    )
    (net (code "71") (name "unconnected-(U1-PA2-Pad16)") (class "Default")
      (node (ref "U1") (pin "16") (pinfunction "PA2_16") (pintype "bidirectional"))
    )
    (net (code "72") (name "unconnected-(U1-PA3-Pad17)") (class "Default")
      (node (ref "U1") (pin "17") (pinfunction "PA3_17") (pintype "bidirectional"))
    )
    (net (code "73") (name "unconnected-(U1-PA4-Pad20)") (class "Default")
      (node (ref "U1") (pin "20") (pinfunction "PA4_20") (pintype "bidirectional"))
    )
    (net (code "74") (name "unconnected-(U1-PA5-Pad21)") (class "Default")
      (node (ref "U1") (pin "21") (pinfunction "PA5_21") (pintype "bidirectional"))
    )
    (net (code "75") (name "unconnected-(U1-PA15-Pad50)") (class "Default")
      (node (ref "U1") (pin "50") (pinfunction "PA15_50") (pintype "bidirectional"))
    )
    (net (code "76") (name "unconnected-(U1-PB0-Pad26)") (class "Default")
      (node (ref "U1") (pin "26") (pinfunction "PB0_26") (pintype "bidirectional"))
    )
    (net (code "77") (name "unconnected-(U1-PB7-Pad59)") (class "Default")
      (node (ref "U1") (pin "59") (pinfunction "PB7_59") (pintype "bidirectional"))
    )
    (net (code "78") (name "unconnected-(U1-PB12-Pad33)") (class "Default")
      (node (ref "U1") (pin "33") (pinfunction "PB12_33") (pintype "bidirectional"))
    )
    (net (code "79") (name "unconnected-(U1-PC0-Pad8)") (class "Default")
      (node (ref "U1") (pin "8") (pinfunction "PC0_8") (pintype "bidirectional"))
    )
    (net (code "80") (name "unconnected-(U1-PC1-Pad9)") (class "Default")
      (node (ref "U1") (pin "9") (pinfunction "PC1_9") (pintype "bidirectional"))
    )
    (net (code "81") (name "unconnected-(U1-PC4-Pad24)") (class "Default")
      (node (ref "U1") (pin "24") (pinfunction "PC4_24") (pintype "bidirectional"))
    )
    (net (code "82") (name "unconnected-(U1-PC5-Pad25)") (class "Default")
      (node (ref "U1") (pin "25") (pinfunction "PC5_25") (pintype "bidirectional"))
    )
    (net (code "83") (name "unconnected-(U1-PC10-Pad51)") (class "Default")
      (node (ref "U1") (pin "51") (pinfunction "PC10_51") (pintype "bidirectional"))
    )
    (net (code "84") (name "unconnected-(U1-PC13-Pad2)") (class "Default")
      (node (ref "U1") (pin "2") (pinfunction "PC13_2") (pintype "bidirectional"))
    )
    (net (code "85") (name "unconnected-(U1-PC14-OSC32_IN-Pad3)") (class "Default")
      (node (ref "U1") (pin "3") (pinfunction "PC14-OSC32_IN_3") (pintype "bidirectional"))
    )
    (net (code "86") (name "unconnected-(U1-PC15-OSC32_OUT-Pad4)") (class "Default")
      (node (ref "U1") (pin "4") (pinfunction "PC15-OSC32_OUT_4") (pintype "bidirectional"))
    )
    (net (code "87") (name "unconnected-(U2-NC-Pad4)") (class "Default")
      (node (ref "U2") (pin "4") (pinfunction "NC_4") (pintype "no_connect"))
    )
  )
)
